# Memory.net
KiCad netlist of a schematic drawn in Altium Designer
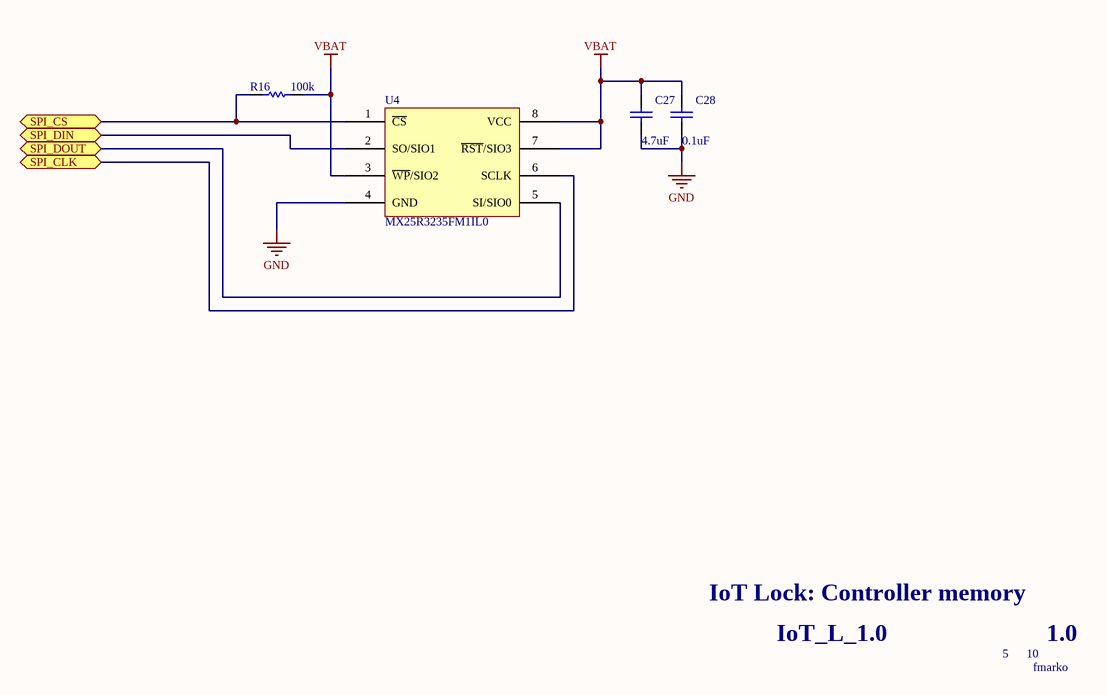
[diagram p0: Memory.SchDoc]

(export (version "E")
  (design (tool "Eeschema 10.0.6"))
  (components
    (comp (ref "C27")
      (value "4.7uF")
      (footprint "0402")
      (description "Capacitor")
      (fields (field (name "Comment") "GRM1555C1HR50BA01D") (field (name "PUBLISHER") "Altium Limited"))
      (libsource (lib "Miscellaneous Devices") (part "Cap"))
    )
    (comp (ref "C28")
      (value "0.1uF")
      (footprint "0402")
      (description "Capacitor")
      (fields (field (name "Comment") "GRM1555C1HR50BA01D") (field (name "PUBLISHER") "Altium Limited"))
      (libsource (lib "Miscellaneous Devices") (part "Cap"))
    )
    (comp (ref "R16")
      (value "100k")
      (footprint "0402")
      (description "Semiconductor Resistor")
      (fields (field (name "Comment") "Res Semi") (field (name "PUBLISHER") "Altium Limited"))
      (libsource (lib "Miscellaneous Devices") (part "Res Semi"))
    )
    (comp (ref "U4")
      (value "MX25R3235FM1IL0")
      (footprint "SOP127P600X175-8N")
      (description "Macronix 32 Mbit SPI Flash memory")
      (libsource (lib "MX25R3235FM1IL0") (part "MX25R3235FM1IL0"))
    )
  )
  (nets
    (net (code "1") (name "/SPI_CLK") (class "Default")
      (node (ref "U4") (pin "6") (pinfunction "SCLK_6") (pintype "passive"))
    )
    (net (code "2") (name "/SPI_CS") (class "Default")
      (node (ref "R16") (pin "1") (pinfunction "1_1") (pintype "passive"))
      (node (ref "U4") (pin "1") (pinfunction "~{CS}_1") (pintype "passive"))
    )
    (net (code "3") (name "/SPI_DIN") (class "Default")
      (node (ref "U4") (pin "2") (pinfunction "SO/SIO1_2") (pintype "passive"))
    )
    (net (code "4") (name "/SPI_DOUT") (class "Default")
      (node (ref "U4") (pin "5") (pinfunction "SI/SIO0_5") (pintype "passive"))
    )
    (net (code "5") (name "GND") (class "Default")
      (node (ref "C27") (pin "1") (pinfunction "1_1") (pintype "passive"))
      (node (ref "C28") (pin "1") (pinfunction "1_1") (pintype "passive"))
      (node (ref "U4") (pin "4") (pinfunction "GND_4") (pintype "passive"))
    )
    (net (code "6") (name "VBAT") (class "Default")
      (node (ref "C27") (pin "2") (pinfunction "2_2") (pintype "passive"))
      (node (ref "C28") (pin "2") (pinfunction "2_2") (pintype "passive"))
      (node (ref "R16") (pin "2") (pinfunction "2_2") (pintype "passive"))
      (node (ref "U4") (pin "3") (pinfunction "~{WP}/SIO2_3") (pintype "passive"))
      (node (ref "U4") (pin "7") (pinfunction "~{RST}/SIO3_7") (pintype "passive"))
      (node (ref "U4") (pin "8") (pinfunction "VCC_8") (pintype "passive"))
    )
  )
)
